# Connector.net
KiCad netlist of a schematic drawn in Altium Designer
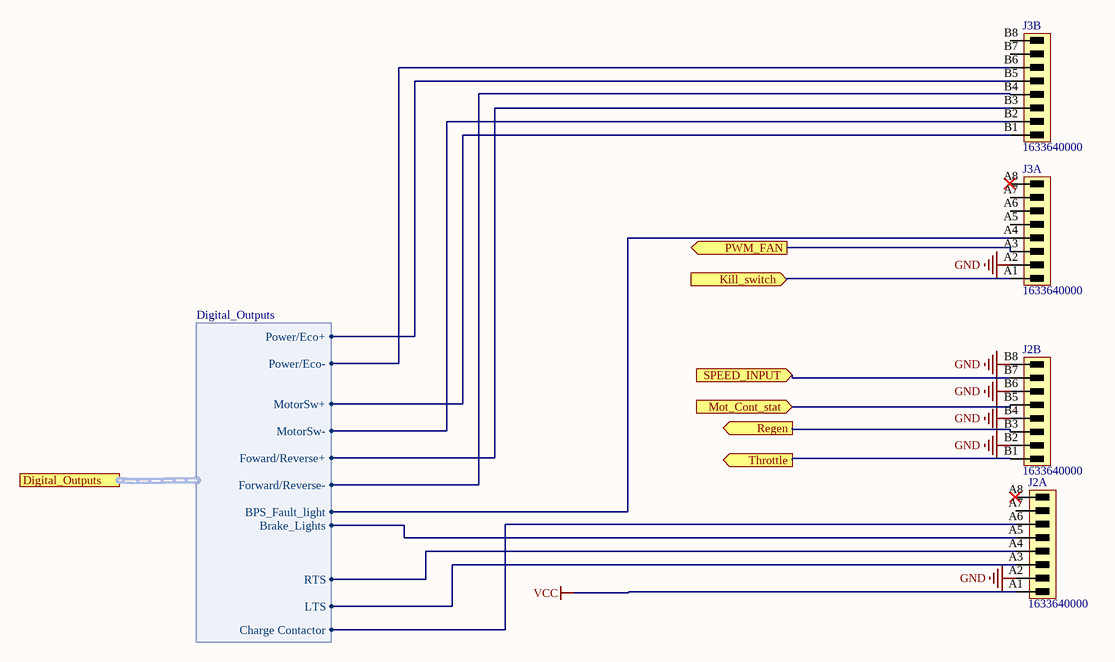
[diagram p0: Connector.SchDoc]

(export (version "E")
  (design (tool "Eeschema 10.0.6"))
  (components
    (comp (ref "J2")
      (value "1633640000")
      (footprint "SLD_3_50_90G_16")
      (description "OMNIMATE Signal - series BL/SL 3.50")
      (fields (field (name "MANUFACTURER") "Weidmueller"))
      (libsource (lib "Altium Content Vault") (part "Header_Male_16_2x08"))
    )
    (comp (ref "J3")
      (value "1633640000")
      (footprint "SLD_3_50_90G_16")
      (description "OMNIMATE Signal - series BL/SL 3.50")
      (fields (field (name "MANUFACTURER") "Weidmueller"))
      (libsource (lib "Altium Content Vault") (part "Header_Male_16_2x08"))
    )
  )
  (nets
    (net (code "2") (name "/BPS_Fault_light") (class "Default")
      (node (ref "J3") (pin "A4") (pinfunction "A4_A4") (pintype "passive"))
    )
    (net (code "3") (name "/Brake_Lights") (class "Default")
      (node (ref "J2") (pin "A5") (pinfunction "A5_A5") (pintype "passive"))
    )
    (net (code "4") (name "/Charge Contactor") (class "Default")
      (node (ref "J2") (pin "A6") (pinfunction "A6_A6") (pintype "passive"))
    )
    (net (code "5") (name "/Forward{slash}Reverse-") (class "Default")
      (node (ref "J3") (pin "B4") (pinfunction "B4_B4") (pintype "passive"))
    )
    (net (code "6") (name "/Foward{slash}Reverse+") (class "Default")
      (node (ref "J3") (pin "B3") (pinfunction "B3_B3") (pintype "passive"))
    )
    (net (code "7") (name "/Kill_switch") (class "Default")
      (node (ref "J3") (pin "A1") (pinfunction "A1_A1") (pintype "passive"))
    )
    (net (code "8") (name "/LTS") (class "Default")
      (node (ref "J2") (pin "A3") (pinfunction "A3_A3") (pintype "passive"))
    )
    (net (code "9") (name "/Mot_Cont_stat") (class "Default")
      (node (ref "J2") (pin "B5") (pinfunction "B5_B5") (pintype "passive"))
    )
    (net (code "10") (name "/MotorSw+") (class "Default")
      (node (ref "J3") (pin "B1") (pinfunction "B1_B1") (pintype "passive"))
    )
    (net (code "11") (name "/MotorSw-") (class "Default")
      (node (ref "J3") (pin "B2") (pinfunction "B2_B2") (pintype "passive"))
    )
    (net (code "12") (name "/PWM_FAN") (class "Default")
      (node (ref "J3") (pin "A3") (pinfunction "A3_A3") (pintype "passive"))
    )
    (net (code "13") (name "/Power{slash}Eco+") (class "Default")
      (node (ref "J3") (pin "B5") (pinfunction "B5_B5") (pintype "passive"))
    )
    (net (code "14") (name "/Power{slash}Eco-") (class "Default")
      (node (ref "J3") (pin "B6") (pinfunction "B6_B6") (pintype "passive"))
    )
    (net (code "15") (name "/RTS") (class "Default")
      (node (ref "J2") (pin "A4") (pinfunction "A4_A4") (pintype "passive"))
    )
    (net (code "16") (name "/Regen") (class "Default")
      (node (ref "J2") (pin "B3") (pinfunction "B3_B3") (pintype "passive"))
    )
    (net (code "17") (name "/SPEED_INPUT") (class "Default")
      (node (ref "J2") (pin "B7") (pinfunction "B7_B7") (pintype "passive"))
    )
    (net (code "18") (name "/Throttle") (class "Default")
      (node (ref "J2") (pin "B1") (pinfunction "B1_B1") (pintype "passive"))
    )
    (net (code "20") (name "GND") (class "Default")
      (node (ref "J2") (pin "A2") (pinfunction "A2_A2") (pintype "passive"))
      (node (ref "J2") (pin "B2") (pinfunction "B2_B2") (pintype "passive"))
      (node (ref "J2") (pin "B4") (pinfunction "B4_B4") (pintype "passive"))
      (node (ref "J2") (pin "B6") (pinfunction "B6_B6") (pintype "passive"))
      (node (ref "J2") (pin "B8") (pinfunction "B8_B8") (pintype "passive"))
      (node (ref "J3") (pin "A2") (pinfunction "A2_A2") (pintype "passive"))
    )
    (net (code "21") (name "VCC") (class "Default")
      (node (ref "J2") (pin "A1") (pinfunction "A1_A1") (pintype "passive"))
    )
    (net (code "22") (name "unconnected-(J2-PadA7)") (class "Default")
      (node (ref "J2") (pin "A7") (pinfunction "A7_A7") (pintype "passive"))
    )
    (net (code "23") (name "unconnected-(J2-PadA8)") (class "Default")
      (node (ref "J2") (pin "A8") (pinfunction "A8_A8") (pintype "passive"))
    )
    (net (code "24") (name "unconnected-(J3-PadA5)") (class "Default")
      (node (ref "J3") (pin "A5") (pinfunction "A5_A5") (pintype "passive"))
    )
    (net (code "25") (name "unconnected-(J3-PadA6)") (class "Default")
      (node (ref "J3") (pin "A6") (pinfunction "A6_A6") (pintype "passive"))
    )
    (net (code "26") (name "unconnected-(J3-PadA7)") (class "Default")
      (node (ref "J3") (pin "A7") (pinfunction "A7_A7") (pintype "passive"))
    )
    (net (code "27") (name "unconnected-(J3-PadA8)") (class "Default")
      (node (ref "J3") (pin "A8") (pinfunction "A8_A8") (pintype "passive"))
    )
    (net (code "28") (name "unconnected-(J3-PadB7)") (class "Default")
      (node (ref "J3") (pin "B7") (pinfunction "B7_B7") (pintype "passive"))
    )
    (net (code "29") (name "unconnected-(J3-PadB8)") (class "Default")
      (node (ref "J3") (pin "B8") (pinfunction "B8_B8") (pintype "passive"))
    )
  )
)
